# 2_5V_and_1_8V_Switches.net
KiCad netlist of a schematic drawn in Altium Designer
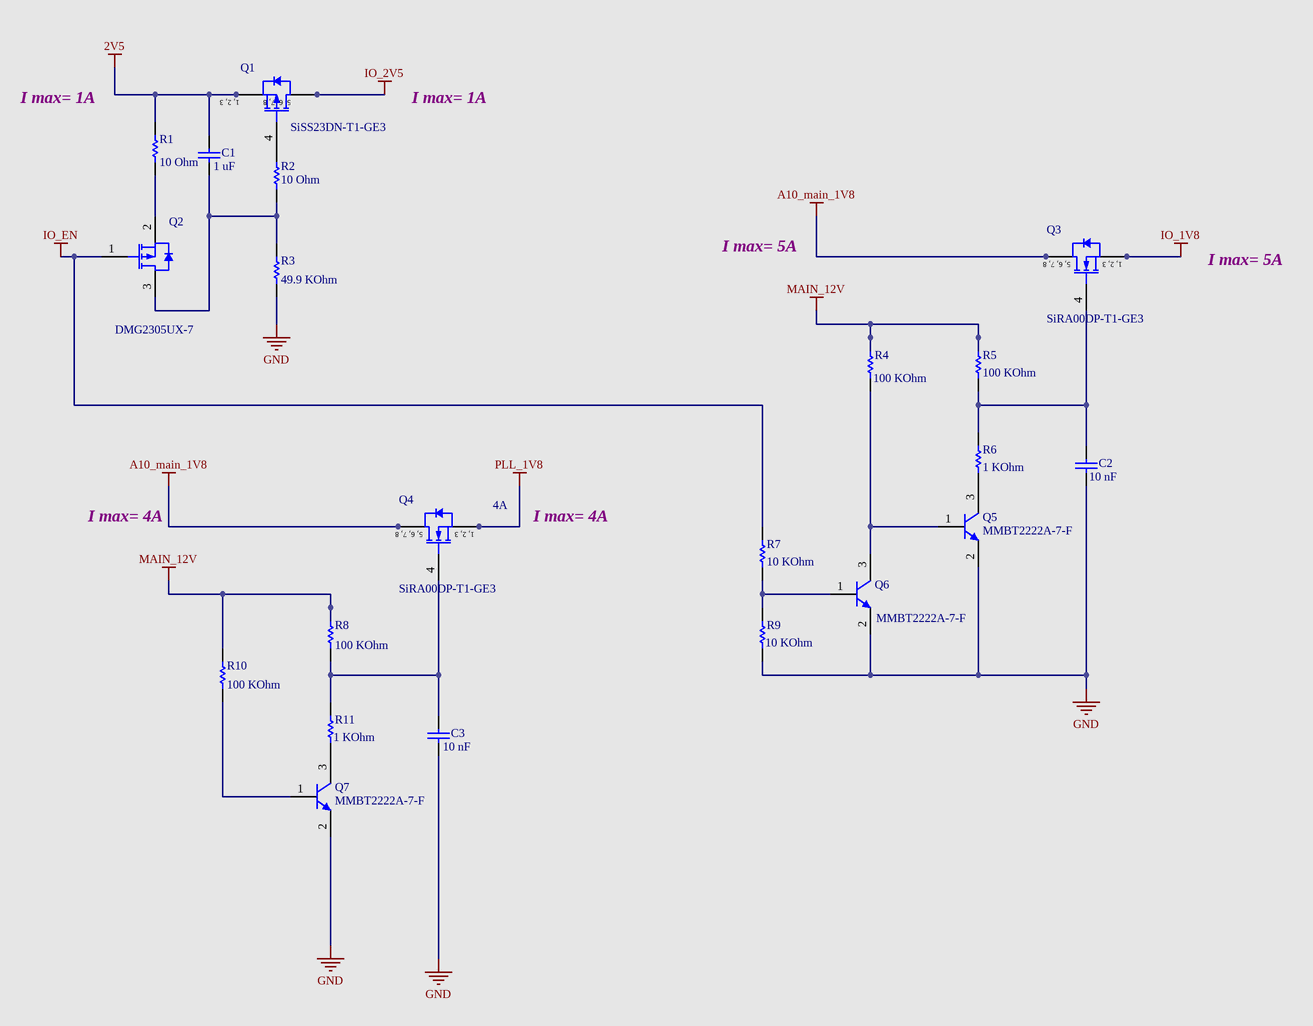
[diagram p0: 2.5V_and_1.8V_Switches.SchDoc]

(export (version "E")
  (design (tool "Eeschema 10.0.6"))
  (components
    (comp (ref "C1")
      (value "CGB2A1X5R1E105K033BC")
      (footprint "CAPC1005X33X10LL5")
      (description "Chip Capacitor, 1 uF, +/- 10%, 25 V, -55 to 85 degC, 0402 (1005 Metric), RoHS, Tape and Reel")
      (fields (field (name "TOLERANCE") "10%") (field (name "CAPACITANCE") "1 uF"))
      (libsource (lib "") (part "CAP-NP-2_1"))
    )
    (comp (ref "C2")
      (value "GRM155R71H103KA88D")
      (footprint "CAPC1005X55X25ML05T10")
      (description "Chip Capacitor, 10 nF, +/- 10%, 50 V, -55 to 125 degC, 0402 (1005 Metric), RoHS, Tape and Reel")
      (fields
        (field (name "TOLERANCE") "10%")
        (field (name "CAPACITANCE") "10 nF")
        (field (name "MANUFACTURER") "Basic Passives")
      )
      (libsource (lib "Altium Content Vault") (part "CAP-NP-2"))
    )
    (comp (ref "C3")
      (value "GRM155R71H103KA88D")
      (footprint "CAPC1005X55X25ML05T10")
      (description "Chip Capacitor, 10 nF, +/- 10%, 50 V, -55 to 125 degC, 0402 (1005 Metric), RoHS, Tape and Reel")
      (fields
        (field (name "TOLERANCE") "10%")
        (field (name "CAPACITANCE") "10 nF")
        (field (name "MANUFACTURER") "Basic Passives")
      )
      (libsource (lib "Altium Content Vault") (part "CAP-NP-2"))
    )
    (comp (ref "Q1")
      (value "SiSS23DN-T1-GE3")
      (footprint "VISH-PPAK1212-8S_V")
      (description "P-Channel MOSFET, 20 V, -50 to 150 degC, 8-Pin SMD (PPAK1212-8S), RoHS, Tape and Reel")
      (libsource (lib "Altium Content Vault") (part "PEMOS-SSSGDDDD-8"))
    )
    (comp (ref "Q2")
      (value "DMG2305UX-7")
      (footprint "DIOD-SOT23-3_A_V")
      (description "P-Channel Enhancement Mode MOSFET, 20 V, -55 to 150 degC, 3-Pin SOT23, RoHS, Tape and Reel")
      (fields (field (name "MANUFACTURER") "Diodes Inc"))
      (libsource (lib "Altium Content Vault") (part "CMP-1693-00002-1"))
    )
    (comp (ref "Q3")
      (value "SiRA00DP-T1-GE3")
      (footprint "VISH-PPAKSO-8_V")
      (description "N-Channe MOSFET, 30 V, -55 to 150 degC, 8-Pin SMD (PPAKSO-8), RoHS, Tape and Reel")
      (libsource (lib "Altium Content Vault") (part "NEMOS-SSSGDDDD-8"))
    )
    (comp (ref "Q4")
      (value "SiRA00DP-T1-GE3")
      (footprint "VISH-PPAKSO-8_V")
      (description "N-Channe MOSFET, 30 V, -55 to 150 degC, 8-Pin SMD (PPAKSO-8), RoHS, Tape and Reel")
      (libsource (lib "Altium Content Vault") (part "NEMOS-SSSGDDDD-8"))
    )
    (comp (ref "Q5")
      (value "MMBT2222A-7-F")
      (footprint "DIOD-SOT23-3_V")
      (description "NPN Small Signal Transistor, 40 V, -55 to 150 degC, 3-Pin SOT23, RoHS, Tape and Reel")
      (fields (field (name "MANUFACTURER") "Diodes Inc"))
      (libsource (lib "Altium Content Vault") (part "BJT-NPN-BEC-3"))
    )
    (comp (ref "Q6")
      (value "MMBT2222A-7-F")
      (footprint "DIOD-SOT23-3_V")
      (description "NPN Small Signal Transistor, 40 V, -55 to 150 degC, 3-Pin SOT23, RoHS, Tape and Reel")
      (fields (field (name "MANUFACTURER") "Diodes Inc"))
      (libsource (lib "Altium Content Vault") (part "BJT-NPN-BEC-3"))
    )
    (comp (ref "Q7")
      (value "MMBT2222A-7-F")
      (footprint "DIOD-SOT23-3_V")
      (description "NPN Small Signal Transistor, 40 V, -55 to 150 degC, 3-Pin SOT23, RoHS, Tape and Reel")
      (fields (field (name "MANUFACTURER") "Diodes Inc"))
      (libsource (lib "Altium Content Vault") (part "BJT-NPN-BEC-3"))
    )
    (comp (ref "R1")
      (value "ERJ-2RKF10R0X")
      (footprint "RESC1005X40X25LL05T05")
      (description "Chip Resistor, 10 Ohm, +/- 1%, 100 mW, -55 to 155 degC, 0402 (1005 Metric), RoHS, Tape and Reel")
      (fields
        (field (name "RESISTANCE") "10 Ohm")
        (field (name "TOLERANCE") "1%")
        (field (name "MANUFACTURER") "Basic Passives")
      )
      (libsource (lib "Altium Content Vault") (part "RES-2"))
    )
    (comp (ref "R2")
      (value "ERJ-2RKF10R0X")
      (footprint "RESC1005X40X25LL05T05")
      (description "Chip Resistor, 10 Ohm, +/- 1%, 100 mW, -55 to 155 degC, 0402 (1005 Metric), RoHS, Tape and Reel")
      (fields
        (field (name "RESISTANCE") "10 Ohm")
        (field (name "TOLERANCE") "1%")
        (field (name "MANUFACTURER") "Basic Passives")
      )
      (libsource (lib "Altium Content Vault") (part "RES-2"))
    )
    (comp (ref "R3")
      (value "ERJ-2RKF4992X")
      (footprint "RESC1005X40X25LL05T05")
      (description "Chip Resistor, 49.9 KOhm, +/- 1%, 100 mW, -55 to 155 degC, 0402 (1005 Metric), RoHS, Tape and Reel")
      (fields
        (field (name "TOLERANCE") "1%")
        (field (name "RESISTANCE") "49.9 KOhm")
        (field (name "MANUFACTURER") "Basic Passives")
      )
      (libsource (lib "Altium Content Vault") (part "RES-2"))
    )
    (comp (ref "R4")
      (value "ERJ-2RKF1003X")
      (footprint "RESC1005X40X25LL05T05")
      (description "Chip Resistor, 100 KOhm, +/- 1%, 100 mW, -55 to 155 degC, 0402 (1005 Metric), RoHS, Tape and Reel")
      (fields
        (field (name "RESISTANCE") "100 KOhm")
        (field (name "TOLERANCE") "1%")
        (field (name "MANUFACTURER") "Basic Passives")
      )
      (libsource (lib "Altium Content Vault") (part "RES-2"))
    )
    (comp (ref "R5")
      (value "ERJ-2RKF1003X")
      (footprint "RESC1005X40X25LL05T05")
      (description "Chip Resistor, 100 KOhm, +/- 1%, 100 mW, -55 to 155 degC, 0402 (1005 Metric), RoHS, Tape and Reel")
      (fields
        (field (name "RESISTANCE") "100 KOhm")
        (field (name "TOLERANCE") "1%")
        (field (name "MANUFACTURER") "Basic Passives")
      )
      (libsource (lib "Altium Content Vault") (part "RES-2"))
    )
    (comp (ref "R6")
      (value "ERJ-2RKF1001X")
      (footprint "RESC1005X40X25LL05T05")
      (description "Chip Resistor, 1 KOhm, +/- 1%, 100 mW, -55 to 155 degC, 0402 (1005 Metric), RoHS, Tape and Reel")
      (fields
        (field (name "RESISTANCE") "1 KOhm")
        (field (name "TOLERANCE") "1%")
        (field (name "MANUFACTURER") "Basic Passives")
      )
      (libsource (lib "Altium Content Vault") (part "RES-2"))
    )
    (comp (ref "R7")
      (value "ERJ-2RKF1002X")
      (footprint "RESC1005X40X25NL05T05")
      (description "Chip Resistor, 10 KOhm, +/- 1%, 100 mW, -55 to 155 degC, 0402 (1005 Metric), RoHS, Tape and Reel")
      (fields
        (field (name "TOLERANCE") "1%")
        (field (name "RESISTANCE") "10 KOhm")
        (field (name "MANUFACTURER") "Basic Passives")
      )
      (libsource (lib "Altium Content Vault") (part "RES-2"))
    )
    (comp (ref "R8")
      (value "ERJ-2RKF1003X")
      (footprint "RESC1005X40X25LL05T05")
      (description "Chip Resistor, 100 KOhm, +/- 1%, 100 mW, -55 to 155 degC, 0402 (1005 Metric), RoHS, Tape and Reel")
      (fields
        (field (name "RESISTANCE") "100 KOhm")
        (field (name "TOLERANCE") "1%")
        (field (name "MANUFACTURER") "Basic Passives")
      )
      (libsource (lib "Altium Content Vault") (part "RES-2"))
    )
    (comp (ref "R9")
      (value "ERJ-2RKF1002X")
      (footprint "RESC1005X40X25NL05T05")
      (description "Chip Resistor, 10 KOhm, +/- 1%, 100 mW, -55 to 155 degC, 0402 (1005 Metric), RoHS, Tape and Reel")
      (fields
        (field (name "TOLERANCE") "1%")
        (field (name "RESISTANCE") "10 KOhm")
        (field (name "MANUFACTURER") "Basic Passives")
      )
      (libsource (lib "Altium Content Vault") (part "RES-2"))
    )
    (comp (ref "R10")
      (value "ERJ-2RKF1003X")
      (footprint "RESC1005X40X25LL05T05")
      (description "Chip Resistor, 100 KOhm, +/- 1%, 100 mW, -55 to 155 degC, 0402 (1005 Metric), RoHS, Tape and Reel")
      (fields
        (field (name "RESISTANCE") "100 KOhm")
        (field (name "TOLERANCE") "1%")
        (field (name "MANUFACTURER") "Basic Passives")
      )
      (libsource (lib "Altium Content Vault") (part "RES-2"))
    )
    (comp (ref "R11")
      (value "ERJ-2RKF1001X")
      (footprint "RESC1005X40X25LL05T05")
      (description "Chip Resistor, 1 KOhm, +/- 1%, 100 mW, -55 to 155 degC, 0402 (1005 Metric), RoHS, Tape and Reel")
      (fields
        (field (name "RESISTANCE") "1 KOhm")
        (field (name "TOLERANCE") "1%")
        (field (name "MANUFACTURER") "Basic Passives")
      )
      (libsource (lib "Altium Content Vault") (part "RES-2"))
    )
  )
  (nets
    (net (code "1") (name "2V5") (class "Default")
      (node (ref "C1") (pin "2") (pinfunction "2_2") (pintype "passive"))
      (node (ref "Q1") (pin "1") (pinfunction "S_1") (pintype "passive"))
      (node (ref "Q1") (pin "2") (pinfunction "S_2") (pintype "passive"))
      (node (ref "Q1") (pin "3") (pinfunction "S_3") (pintype "passive"))
      (node (ref "R1") (pin "2") (pinfunction "2_2") (pintype "passive"))
    )
    (net (code "2") (name "A10_main_1V8") (class "Default")
      (node (ref "Q3") (pin "5") (pinfunction "D_5") (pintype "passive"))
      (node (ref "Q3") (pin "6") (pinfunction "D_6") (pintype "passive"))
      (node (ref "Q3") (pin "7") (pinfunction "D_7") (pintype "passive"))
      (node (ref "Q3") (pin "8") (pinfunction "D_8") (pintype "passive"))
      (node (ref "Q4") (pin "5") (pinfunction "D_5") (pintype "passive"))
      (node (ref "Q4") (pin "6") (pinfunction "D_6") (pintype "passive"))
      (node (ref "Q4") (pin "7") (pinfunction "D_7") (pintype "passive"))
      (node (ref "Q4") (pin "8") (pinfunction "D_8") (pintype "passive"))
    )
    (net (code "3") (name "GND") (class "Default")
      (node (ref "C2") (pin "1") (pinfunction "1_1") (pintype "passive"))
      (node (ref "C3") (pin "1") (pinfunction "1_1") (pintype "passive"))
      (node (ref "Q5") (pin "2") (pinfunction "E_2") (pintype "passive"))
      (node (ref "Q6") (pin "2") (pinfunction "E_2") (pintype "passive"))
      (node (ref "Q7") (pin "2") (pinfunction "E_2") (pintype "passive"))
      (node (ref "R3") (pin "1") (pinfunction "1_1") (pintype "passive"))
      (node (ref "R9") (pin "1") (pinfunction "1_1") (pintype "passive"))
    )
    (net (code "4") (name "IO_1V8") (class "Default")
      (node (ref "Q3") (pin "1") (pinfunction "S_1") (pintype "passive"))
      (node (ref "Q3") (pin "2") (pinfunction "S_2") (pintype "passive"))
      (node (ref "Q3") (pin "3") (pinfunction "S_3") (pintype "passive"))
    )
    (net (code "5") (name "IO_2V5") (class "Default")
      (node (ref "Q1") (pin "5") (pinfunction "D_5") (pintype "passive"))
      (node (ref "Q1") (pin "6") (pinfunction "D_6") (pintype "passive"))
      (node (ref "Q1") (pin "7") (pinfunction "D_7") (pintype "passive"))
      (node (ref "Q1") (pin "8") (pinfunction "D_8") (pintype "passive"))
    )
    (net (code "6") (name "IO_EN") (class "Default")
      (node (ref "Q2") (pin "1") (pinfunction "GATE_1") (pintype "passive"))
      (node (ref "R7") (pin "2") (pinfunction "2_2") (pintype "passive"))
    )
    (net (code "7") (name "MAIN_12V") (class "Default")
      (node (ref "R10") (pin "2") (pinfunction "2_2") (pintype "passive"))
      (node (ref "R4") (pin "2") (pinfunction "2_2") (pintype "passive"))
      (node (ref "R5") (pin "2") (pinfunction "2_2") (pintype "passive"))
      (node (ref "R8") (pin "2") (pinfunction "2_2") (pintype "passive"))
    )
    (net (code "8") (name "Net-(Q1-G)") (class "Default")
      (node (ref "Q1") (pin "4") (pinfunction "G_4") (pintype "passive"))
      (node (ref "R2") (pin "2") (pinfunction "2_2") (pintype "passive"))
    )
    (net (code "9") (name "Net-(Q2-DRAIN)") (class "Default")
      (node (ref "C1") (pin "1") (pinfunction "1_1") (pintype "passive"))
      (node (ref "Q2") (pin "3") (pinfunction "DRAIN_3") (pintype "passive"))
      (node (ref "R2") (pin "1") (pinfunction "1_1") (pintype "passive"))
      (node (ref "R3") (pin "2") (pinfunction "2_2") (pintype "passive"))
    )
    (net (code "10") (name "Net-(Q2-SOURCE)") (class "Default")
      (node (ref "Q2") (pin "2") (pinfunction "SOURCE_2") (pintype "passive"))
      (node (ref "R1") (pin "1") (pinfunction "1_1") (pintype "passive"))
    )
    (net (code "11") (name "Net-(Q3-G)") (class "Default")
      (node (ref "C2") (pin "2") (pinfunction "2_2") (pintype "passive"))
      (node (ref "Q3") (pin "4") (pinfunction "G_4") (pintype "passive"))
      (node (ref "R5") (pin "1") (pinfunction "1_1") (pintype "passive"))
      (node (ref "R6") (pin "2") (pinfunction "2_2") (pintype "passive"))
    )
    (net (code "12") (name "Net-(Q4-G)") (class "Default")
      (node (ref "C3") (pin "2") (pinfunction "2_2") (pintype "passive"))
      (node (ref "Q4") (pin "4") (pinfunction "G_4") (pintype "passive"))
      (node (ref "R11") (pin "2") (pinfunction "2_2") (pintype "passive"))
      (node (ref "R8") (pin "1") (pinfunction "1_1") (pintype "passive"))
    )
    (net (code "13") (name "Net-(Q5-B)") (class "Default")
      (node (ref "Q5") (pin "1") (pinfunction "B_1") (pintype "passive"))
      (node (ref "Q6") (pin "3") (pinfunction "C_3") (pintype "passive"))
      (node (ref "R4") (pin "1") (pinfunction "1_1") (pintype "passive"))
    )
    (net (code "14") (name "Net-(Q5-C)") (class "Default")
      (node (ref "Q5") (pin "3") (pinfunction "C_3") (pintype "passive"))
      (node (ref "R6") (pin "1") (pinfunction "1_1") (pintype "passive"))
    )
    (net (code "15") (name "Net-(Q6-B)") (class "Default")
      (node (ref "Q6") (pin "1") (pinfunction "B_1") (pintype "passive"))
      (node (ref "R7") (pin "1") (pinfunction "1_1") (pintype "passive"))
      (node (ref "R9") (pin "2") (pinfunction "2_2") (pintype "passive"))
    )
    (net (code "16") (name "Net-(Q7-B)") (class "Default")
      (node (ref "Q7") (pin "1") (pinfunction "B_1") (pintype "passive"))
      (node (ref "R10") (pin "1") (pinfunction "1_1") (pintype "passive"))
    )
    (net (code "17") (name "Net-(Q7-C)") (class "Default")
      (node (ref "Q7") (pin "3") (pinfunction "C_3") (pintype "passive"))
      (node (ref "R11") (pin "1") (pinfunction "1_1") (pintype "passive"))
    )
    (net (code "18") (name "PLL_1V8") (class "Default")
      (node (ref "Q4") (pin "1") (pinfunction "S_1") (pintype "passive"))
      (node (ref "Q4") (pin "2") (pinfunction "S_2") (pintype "passive"))
      (node (ref "Q4") (pin "3") (pinfunction "S_3") (pintype "passive"))
    )
  )
)
